# nixie_2020_mainboard_v3_6digit.net
KiCad netlist of a schematic drawn in EAGLE
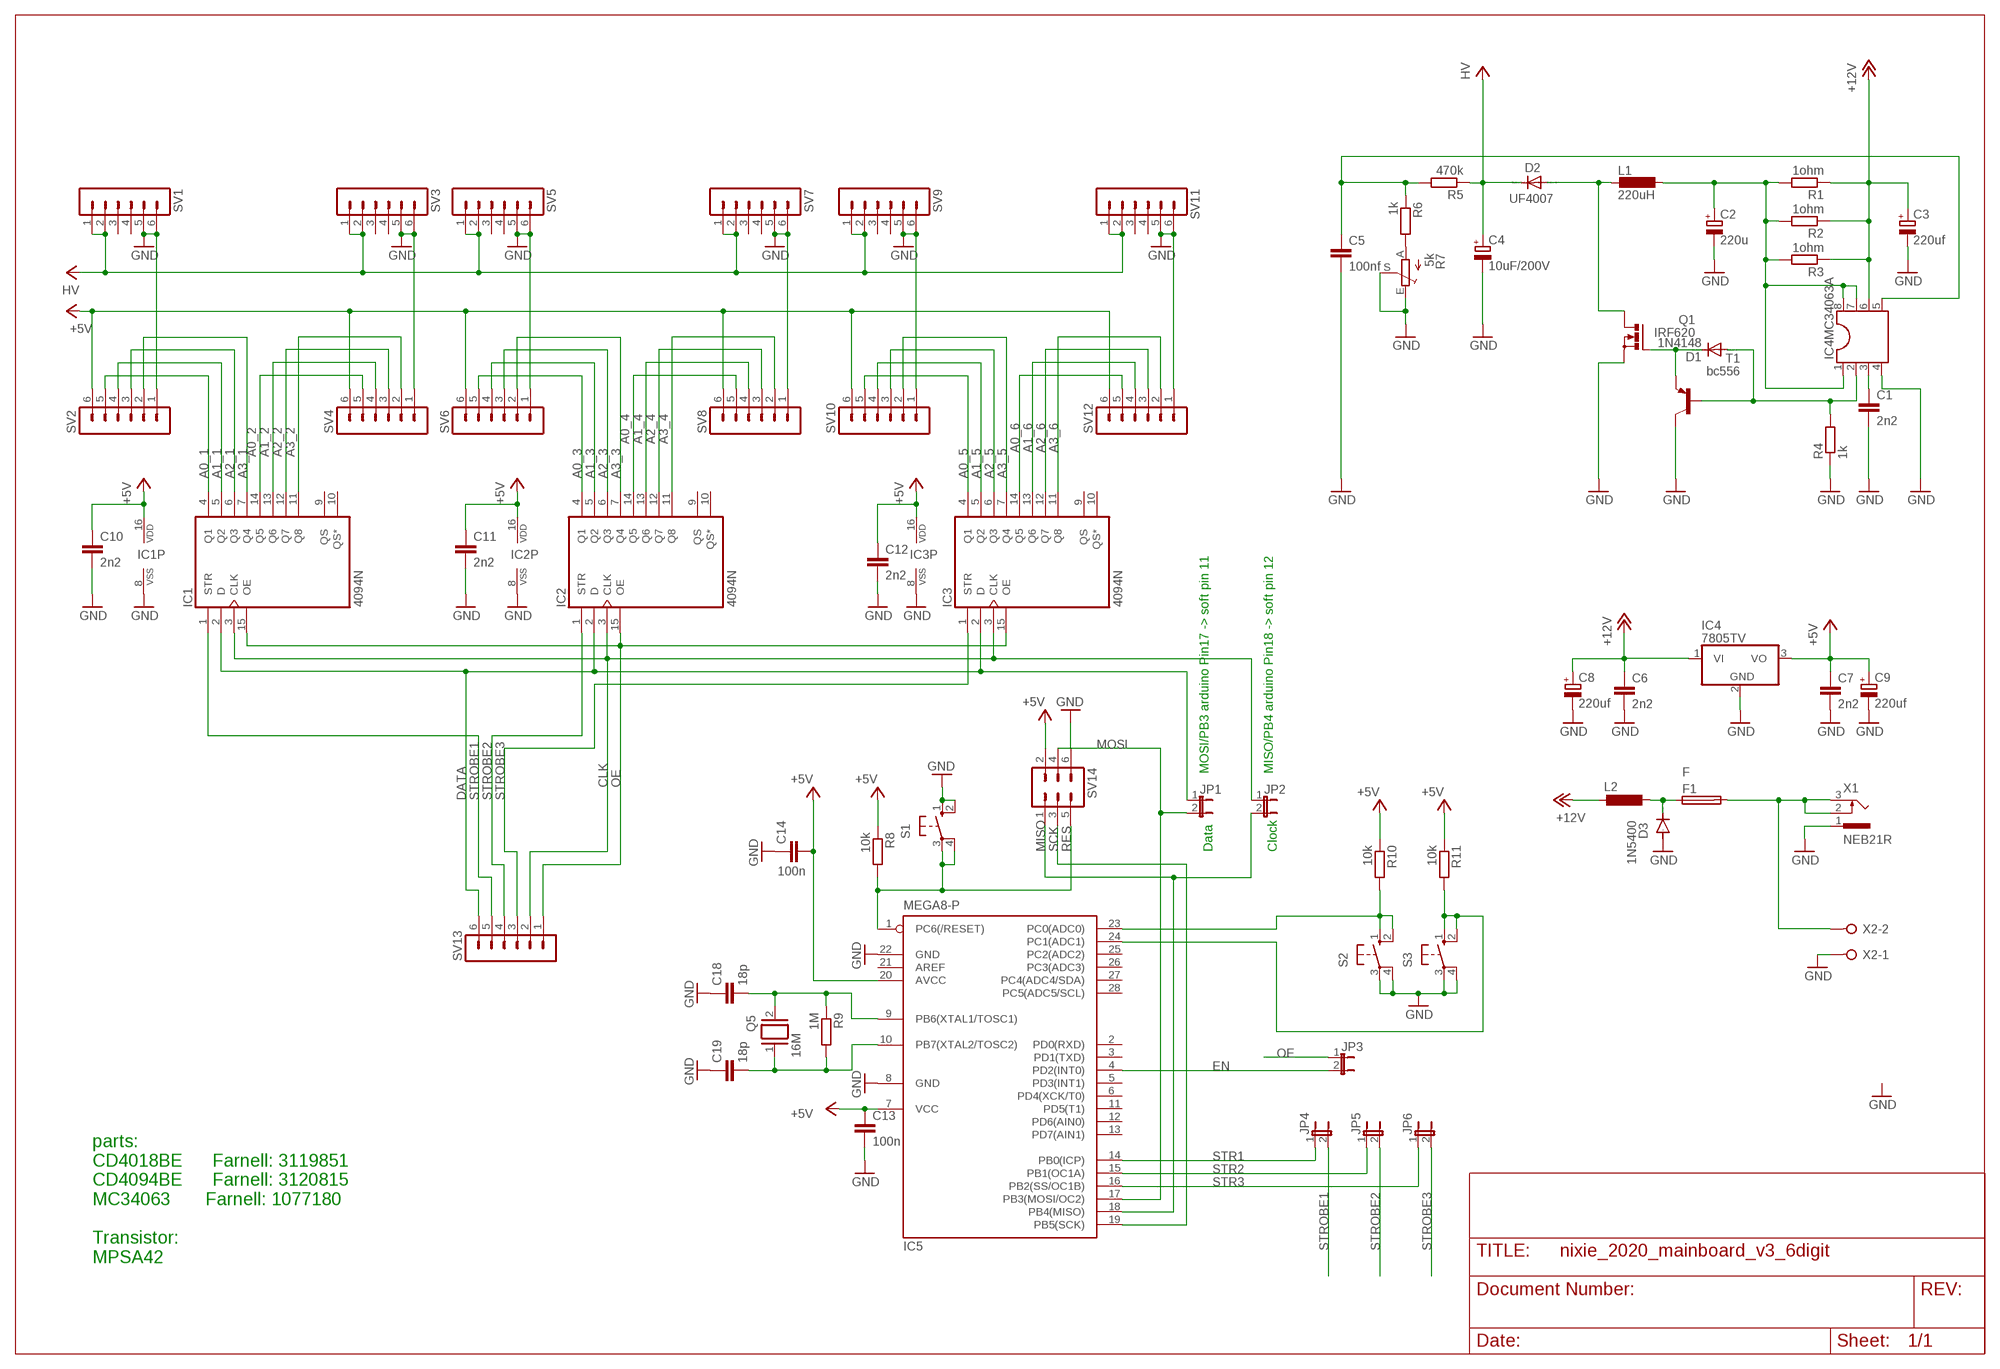
[diagram p0: schematic, sheet 1]

(export (version "E")
  (design (tool "Eeschema 10.0.6"))
  (components
    (comp (ref "C1")
      (value "2n2")
      (footprint "eagle-import:C050-030X075")
      (libsource (lib "eagle-import") (part "C-EU050-030X075"))
    )
    (comp (ref "C2")
      (value "220u")
      (footprint "eagle-import:E5-10,5")
      (libsource (lib "eagle-import") (part "CPOL-EUE5-10.5"))
    )
    (comp (ref "C3")
      (value "220uf")
      (footprint "eagle-import:E5-10,5")
      (libsource (lib "eagle-import") (part "CPOL-EUE5-10.5"))
    )
    (comp (ref "C4")
      (value "10uF/200V")
      (footprint "eagle-import:E5-10,5")
      (libsource (lib "eagle-import") (part "CPOL-EUE5-10.5"))
    )
    (comp (ref "C5")
      (value "100nf")
      (footprint "eagle-import:C075-042X103")
      (libsource (lib "eagle-import") (part "C-EU075-042X103"))
    )
    (comp (ref "C6")
      (value "2n2")
      (footprint "eagle-import:C050-030X075")
      (libsource (lib "eagle-import") (part "C-EU050-030X075"))
    )
    (comp (ref "C7")
      (value "2n2")
      (footprint "eagle-import:C050-030X075")
      (libsource (lib "eagle-import") (part "C-EU050-030X075"))
    )
    (comp (ref "C8")
      (value "220uf")
      (footprint "eagle-import:E5-10,5")
      (libsource (lib "eagle-import") (part "CPOL-EUE5-10.5"))
    )
    (comp (ref "C9")
      (value "220uf")
      (footprint "eagle-import:E5-10,5")
      (libsource (lib "eagle-import") (part "CPOL-EUE5-10.5"))
    )
    (comp (ref "C10")
      (value "2n2")
      (footprint "eagle-import:C050-030X075")
      (libsource (lib "eagle-import") (part "C-EU050-030X075"))
    )
    (comp (ref "C11")
      (value "2n2")
      (footprint "eagle-import:C050-030X075")
      (libsource (lib "eagle-import") (part "C-EU050-030X075"))
    )
    (comp (ref "C12")
      (value "2n2")
      (footprint "eagle-import:C050-030X075")
      (libsource (lib "eagle-import") (part "C-EU050-030X075"))
    )
    (comp (ref "C13")
      (value "100n")
      (footprint "eagle-import:C050-025X075")
      (libsource (lib "eagle-import") (part "resistor_C-EU050-025X075"))
    )
    (comp (ref "C14")
      (value "100n")
      (footprint "eagle-import:C050-025X075")
      (libsource (lib "eagle-import") (part "resistor_C-EU050-025X075"))
    )
    (comp (ref "C18")
      (value "18p")
      (footprint "eagle-import:C050-025X075")
      (libsource (lib "eagle-import") (part "resistor_C-EU050-025X075"))
    )
    (comp (ref "C19")
      (value "18p")
      (footprint "eagle-import:C050-025X075")
      (libsource (lib "eagle-import") (part "resistor_C-EU050-025X075"))
    )
    (comp (ref "D1")
      (value "1N4148")
      (footprint "eagle-import:DO35-10")
      (libsource (lib "eagle-import") (part "1N4148DO35-10"))
    )
    (comp (ref "D2")
      (value "UF4007")
      (footprint "eagle-import:DO35-10")
      (libsource (lib "eagle-import") (part "BAV21"))
    )
    (comp (ref "D3")
      (value "1N5400")
      (footprint "eagle-import:DO201-15")
      (libsource (lib "eagle-import") (part "1N5400"))
    )
    (comp (ref "F1")
      (value "F")
      (footprint "eagle-import:SHK20L")
      (libsource (lib "eagle-import") (part "FUSESHK20L"))
    )
    (comp (ref "IC1")
      (value "4094N")
      (footprint "eagle-import:DIL16")
      (libsource (lib "eagle-import") (part "4094N"))
    )
    (comp (ref "IC2")
      (value "4094N")
      (footprint "eagle-import:DIL16")
      (libsource (lib "eagle-import") (part "4094N"))
    )
    (comp (ref "IC3")
      (value "4094N")
      (footprint "eagle-import:DIL16")
      (libsource (lib "eagle-import") (part "4094N"))
    )
    (comp (ref "IC4")
      (value "7805TV")
      (footprint "eagle-import:TO220V")
      (libsource (lib "eagle-import") (part "78TV05"))
    )
    (comp (ref "IC4MC34063A")
      (value "DIL8S")
      (footprint "eagle-import:SOCKET-08")
      (libsource (lib "eagle-import") (part "DIL8S"))
    )
    (comp (ref "IC5")
      (value "MEGA8-P")
      (footprint "eagle-import:DIL28-3")
      (libsource (lib "eagle-import") (part "MEGA8-P"))
    )
    (comp (ref "JP1")
      (value "JP1E")
      (footprint "eagle-import:JP1")
      (libsource (lib "eagle-import") (part "JP1E"))
    )
    (comp (ref "JP2")
      (value "JP1E")
      (footprint "eagle-import:JP1")
      (libsource (lib "eagle-import") (part "JP1E"))
    )
    (comp (ref "JP3")
      (value "JP1E")
      (footprint "eagle-import:JP1")
      (libsource (lib "eagle-import") (part "JP1E"))
    )
    (comp (ref "JP4")
      (value "JP1E")
      (footprint "eagle-import:JP1")
      (libsource (lib "eagle-import") (part "JP1E"))
    )
    (comp (ref "JP5")
      (value "JP1E")
      (footprint "eagle-import:JP1")
      (libsource (lib "eagle-import") (part "JP1E"))
    )
    (comp (ref "JP6")
      (value "JP1E")
      (footprint "eagle-import:JP1")
      (libsource (lib "eagle-import") (part "JP1E"))
    )
    (comp (ref "L1")
      (value "220uH")
      (footprint "eagle-import:LAN02KR")
      (libsource (lib "eagle-import") (part "L-EULAN02KR"))
    )
    (comp (ref "L2")
      (value "L-EU0207/10")
      (footprint "eagle-import:0207_10")
      (libsource (lib "eagle-import") (part "rcl_334_L-EU0207/10"))
    )
    (comp (ref "Q1")
      (value "IRF620")
      (footprint "eagle-import:TO220BV")
      (libsource (lib "eagle-import") (part "IRF512"))
    )
    (comp (ref "Q5")
      (value "16M")
      (footprint "eagle-import:QS")
      (libsource (lib "eagle-import") (part "XTAL/S"))
    )
    (comp (ref "R1")
      (value "1ohm")
      (footprint "eagle-import:0207_12")
      (libsource (lib "eagle-import") (part "R-EU_0207/12"))
    )
    (comp (ref "R2")
      (value "1ohm")
      (footprint "eagle-import:0207_12")
      (libsource (lib "eagle-import") (part "R-EU_0207/12"))
    )
    (comp (ref "R3")
      (value "1ohm")
      (footprint "eagle-import:0207_12")
      (libsource (lib "eagle-import") (part "R-EU_0207/12"))
    )
    (comp (ref "R4")
      (value "1k")
      (footprint "eagle-import:0207_12")
      (libsource (lib "eagle-import") (part "R-EU_0207/12"))
    )
    (comp (ref "R5")
      (value "470k")
      (footprint "eagle-import:0207_12")
      (libsource (lib "eagle-import") (part "R-EU_0207/12"))
    )
    (comp (ref "R6")
      (value "1k")
      (footprint "eagle-import:0207_12")
      (libsource (lib "eagle-import") (part "R-EU_0207/12"))
    )
    (comp (ref "R7")
      (value "5k")
      (footprint "eagle-import:RJ9W")
      (libsource (lib "eagle-import") (part "TRIM_EU-RJ9W"))
    )
    (comp (ref "R8")
      (value "10k")
      (footprint "eagle-import:0207_12")
      (libsource (lib "eagle-import") (part "R-EU_0207/12"))
    )
    (comp (ref "R9")
      (value "1M")
      (footprint "eagle-import:0207_12")
      (libsource (lib "eagle-import") (part "R-EU_0207/12"))
    )
    (comp (ref "R10")
      (value "10k")
      (footprint "eagle-import:0207_12")
      (libsource (lib "eagle-import") (part "R-EU_0207/12"))
    )
    (comp (ref "R11")
      (value "10k")
      (footprint "eagle-import:0207_12")
      (libsource (lib "eagle-import") (part "R-EU_0207/12"))
    )
    (comp (ref "S1")
      (value "10-XX")
      (footprint "eagle-import:B3F-10XX")
      (fields (field (name "MPN") "B3F-1000"))
      (libsource (lib "eagle-import") (part "10-XX"))
    )
    (comp (ref "S2")
      (value "10-XX")
      (footprint "eagle-import:B3F-10XX")
      (fields (field (name "MPN") "B3F-1000"))
      (libsource (lib "eagle-import") (part "10-XX"))
    )
    (comp (ref "S3")
      (value "10-XX")
      (footprint "eagle-import:B3F-10XX")
      (fields (field (name "MPN") "B3F-1000"))
      (libsource (lib "eagle-import") (part "10-XX"))
    )
    (comp (ref "SV1")
      (value "MA06-1")
      (footprint "eagle-import:MA06-1")
      (libsource (lib "eagle-import") (part "MA06-1"))
    )
    (comp (ref "SV2")
      (value "MA06-1")
      (footprint "eagle-import:MA06-1")
      (libsource (lib "eagle-import") (part "MA06-1"))
    )
    (comp (ref "SV3")
      (value "MA06-1")
      (footprint "eagle-import:MA06-1")
      (libsource (lib "eagle-import") (part "MA06-1"))
    )
    (comp (ref "SV4")
      (value "MA06-1")
      (footprint "eagle-import:MA06-1")
      (libsource (lib "eagle-import") (part "MA06-1"))
    )
    (comp (ref "SV5")
      (value "MA06-1")
      (footprint "eagle-import:MA06-1")
      (libsource (lib "eagle-import") (part "MA06-1"))
    )
    (comp (ref "SV6")
      (value "MA06-1")
      (footprint "eagle-import:MA06-1")
      (libsource (lib "eagle-import") (part "MA06-1"))
    )
    (comp (ref "SV7")
      (value "MA06-1")
      (footprint "eagle-import:MA06-1")
      (libsource (lib "eagle-import") (part "MA06-1"))
    )
    (comp (ref "SV8")
      (value "MA06-1")
      (footprint "eagle-import:MA06-1")
      (libsource (lib "eagle-import") (part "MA06-1"))
    )
    (comp (ref "SV9")
      (value "MA06-1")
      (footprint "eagle-import:MA06-1")
      (libsource (lib "eagle-import") (part "MA06-1"))
    )
    (comp (ref "SV10")
      (value "MA06-1")
      (footprint "eagle-import:MA06-1")
      (libsource (lib "eagle-import") (part "MA06-1"))
    )
    (comp (ref "SV11")
      (value "MA06-1")
      (footprint "eagle-import:MA06-1")
      (libsource (lib "eagle-import") (part "MA06-1"))
    )
    (comp (ref "SV12")
      (value "MA06-1")
      (footprint "eagle-import:MA06-1")
      (libsource (lib "eagle-import") (part "MA06-1"))
    )
    (comp (ref "SV13")
      (value "MA06-1")
      (footprint "eagle-import:MA06-1")
      (libsource (lib "eagle-import") (part "MA06-1"))
    )
    (comp (ref "SV14")
      (value "MA03-2")
      (footprint "eagle-import:MA03-2")
      (libsource (lib "eagle-import") (part "MA03-2"))
    )
    (comp (ref "T1")
      (value "bc556")
      (footprint "eagle-import:TO92-EBC")
      (libsource (lib "eagle-import") (part "-PNP-TO92-EBCBC556A"))
    )
    (comp (ref "X1")
      (value "NEB21R")
      (footprint "eagle-import:NEB21R")
      (fields (field (name "MPN") "NEB 21 R"))
      (libsource (lib "eagle-import") (part "NEB21R"))
    )
    (comp (ref "X2")
      (value "W237-02P")
      (footprint "eagle-import:W237-132")
      (libsource (lib "eagle-import") (part "W237-02P"))
    )
  )
  (nets
    (net (code "1") (name "+5V") (class "Default")
      (node (ref "C10") (pin "1") (pinfunction "1_1") (pintype "passive"))
      (node (ref "C11") (pin "1") (pinfunction "1_1") (pintype "passive"))
      (node (ref "C12") (pin "1") (pinfunction "1_1") (pintype "passive"))
      (node (ref "C13") (pin "1") (pinfunction "1_1") (pintype "passive"))
      (node (ref "C14") (pin "2") (pinfunction "2_2") (pintype "passive"))
      (node (ref "C7") (pin "1") (pinfunction "1_1") (pintype "passive"))
      (node (ref "C9") (pin "+") (pinfunction "+_+") (pintype "passive"))
      (node (ref "IC1") (pin "16") (pinfunction "VDD_16") (pintype "power_in"))
      (node (ref "IC2") (pin "16") (pinfunction "VDD_16") (pintype "power_in"))
      (node (ref "IC3") (pin "16") (pinfunction "VDD_16") (pintype "power_in"))
      (node (ref "IC4") (pin "3") (pinfunction "VO_3") (pintype "passive"))
      (node (ref "IC5") (pin "20") (pinfunction "AVCC_20") (pintype "power_in"))
      (node (ref "IC5") (pin "7") (pinfunction "VCC_7") (pintype "power_in"))
      (node (ref "R10") (pin "1") (pinfunction "1_1") (pintype "passive"))
      (node (ref "R11") (pin "1") (pinfunction "1_1") (pintype "passive"))
      (node (ref "R8") (pin "1") (pinfunction "1_1") (pintype "passive"))
      (node (ref "SV10") (pin "6") (pinfunction "6_6") (pintype "passive"))
      (node (ref "SV12") (pin "6") (pinfunction "6_6") (pintype "passive"))
      (node (ref "SV14") (pin "2") (pinfunction "2_2") (pintype "passive"))
      (node (ref "SV2") (pin "6") (pinfunction "6_6") (pintype "passive"))
      (node (ref "SV4") (pin "6") (pinfunction "6_6") (pintype "passive"))
      (node (ref "SV6") (pin "6") (pinfunction "6_6") (pintype "passive"))
      (node (ref "SV8") (pin "6") (pinfunction "6_6") (pintype "passive"))
    )
    (net (code "2") (name "+12V") (class "Default")
      (node (ref "C3") (pin "+") (pinfunction "+_+") (pintype "passive"))
      (node (ref "C6") (pin "1") (pinfunction "1_1") (pintype "passive"))
      (node (ref "C8") (pin "+") (pinfunction "+_+") (pintype "passive"))
      (node (ref "IC4") (pin "1") (pinfunction "VI_1") (pintype "input"))
      (node (ref "IC4MC34063A") (pin "6") (pinfunction "6_6") (pintype "passive"))
      (node (ref "L2") (pin "1") (pinfunction "1_1") (pintype "passive"))
      (node (ref "R1") (pin "1") (pinfunction "1_1") (pintype "passive"))
      (node (ref "R2") (pin "1") (pinfunction "1_1") (pintype "passive"))
      (node (ref "R3") (pin "1") (pinfunction "1_1") (pintype "passive"))
    )
    (net (code "3") (name "/A0_1") (class "Default")
      (node (ref "IC1") (pin "4") (pinfunction "Q1_4") (pintype "output"))
      (node (ref "SV2") (pin "5") (pinfunction "5_5") (pintype "passive"))
    )
    (net (code "4") (name "/A0_2") (class "Default")
      (node (ref "IC1") (pin "14") (pinfunction "Q5_14") (pintype "output"))
      (node (ref "SV4") (pin "5") (pinfunction "5_5") (pintype "passive"))
    )
    (net (code "5") (name "/A0_3") (class "Default")
      (node (ref "IC2") (pin "4") (pinfunction "Q1_4") (pintype "output"))
      (node (ref "SV6") (pin "5") (pinfunction "5_5") (pintype "passive"))
    )
    (net (code "6") (name "/A0_4") (class "Default")
      (node (ref "IC2") (pin "14") (pinfunction "Q5_14") (pintype "output"))
      (node (ref "SV8") (pin "5") (pinfunction "5_5") (pintype "passive"))
    )
    (net (code "7") (name "/A0_5") (class "Default")
      (node (ref "IC3") (pin "4") (pinfunction "Q1_4") (pintype "output"))
      (node (ref "SV10") (pin "5") (pinfunction "5_5") (pintype "passive"))
    )
    (net (code "8") (name "/A0_6") (class "Default")
      (node (ref "IC3") (pin "14") (pinfunction "Q5_14") (pintype "output"))
      (node (ref "SV12") (pin "5") (pinfunction "5_5") (pintype "passive"))
    )
    (net (code "9") (name "/A1_1") (class "Default")
      (node (ref "IC1") (pin "5") (pinfunction "Q2_5") (pintype "output"))
      (node (ref "SV2") (pin "4") (pinfunction "4_4") (pintype "passive"))
    )
    (net (code "10") (name "/A1_2") (class "Default")
      (node (ref "IC1") (pin "13") (pinfunction "Q6_13") (pintype "output"))
      (node (ref "SV4") (pin "4") (pinfunction "4_4") (pintype "passive"))
    )
    (net (code "11") (name "/A1_3") (class "Default")
      (node (ref "IC2") (pin "5") (pinfunction "Q2_5") (pintype "output"))
      (node (ref "SV6") (pin "4") (pinfunction "4_4") (pintype "passive"))
    )
    (net (code "12") (name "/A1_4") (class "Default")
      (node (ref "IC2") (pin "13") (pinfunction "Q6_13") (pintype "output"))
      (node (ref "SV8") (pin "4") (pinfunction "4_4") (pintype "passive"))
    )
    (net (code "13") (name "/A1_5") (class "Default")
      (node (ref "IC3") (pin "5") (pinfunction "Q2_5") (pintype "output"))
      (node (ref "SV10") (pin "4") (pinfunction "4_4") (pintype "passive"))
    )
    (net (code "14") (name "/A1_6") (class "Default")
      (node (ref "IC3") (pin "13") (pinfunction "Q6_13") (pintype "output"))
      (node (ref "SV12") (pin "4") (pinfunction "4_4") (pintype "passive"))
    )
    (net (code "15") (name "/A2_1") (class "Default")
      (node (ref "IC1") (pin "6") (pinfunction "Q3_6") (pintype "output"))
      (node (ref "SV2") (pin "3") (pinfunction "3_3") (pintype "passive"))
    )
    (net (code "16") (name "/A2_2") (class "Default")
      (node (ref "IC1") (pin "12") (pinfunction "Q7_12") (pintype "output"))
      (node (ref "SV4") (pin "3") (pinfunction "3_3") (pintype "passive"))
    )
    (net (code "17") (name "/A2_3") (class "Default")
      (node (ref "IC2") (pin "6") (pinfunction "Q3_6") (pintype "output"))
      (node (ref "SV6") (pin "3") (pinfunction "3_3") (pintype "passive"))
    )
    (net (code "18") (name "/A2_4") (class "Default")
      (node (ref "IC2") (pin "12") (pinfunction "Q7_12") (pintype "output"))
      (node (ref "SV8") (pin "3") (pinfunction "3_3") (pintype "passive"))
    )
    (net (code "19") (name "/A2_5") (class "Default")
      (node (ref "IC3") (pin "6") (pinfunction "Q3_6") (pintype "output"))
      (node (ref "SV10") (pin "3") (pinfunction "3_3") (pintype "passive"))
    )
    (net (code "20") (name "/A2_6") (class "Default")
      (node (ref "IC3") (pin "12") (pinfunction "Q7_12") (pintype "output"))
      (node (ref "SV12") (pin "3") (pinfunction "3_3") (pintype "passive"))
    )
    (net (code "21") (name "/A3_1") (class "Default")
      (node (ref "IC1") (pin "7") (pinfunction "Q4_7") (pintype "output"))
      (node (ref "SV2") (pin "2") (pinfunction "2_2") (pintype "passive"))
    )
    (net (code "22") (name "/A3_2") (class "Default")
      (node (ref "IC1") (pin "11") (pinfunction "Q8_11") (pintype "output"))
      (node (ref "SV4") (pin "2") (pinfunction "2_2") (pintype "passive"))
    )
    (net (code "23") (name "/A3_3") (class "Default")
      (node (ref "IC2") (pin "7") (pinfunction "Q4_7") (pintype "output"))
      (node (ref "SV6") (pin "2") (pinfunction "2_2") (pintype "passive"))
    )
    (net (code "24") (name "/A3_4") (class "Default")
      (node (ref "IC2") (pin "11") (pinfunction "Q8_11") (pintype "output"))
      (node (ref "SV8") (pin "2") (pinfunction "2_2") (pintype "passive"))
    )
    (net (code "25") (name "/A3_5") (class "Default")
      (node (ref "IC3") (pin "7") (pinfunction "Q4_7") (pintype "output"))
      (node (ref "SV10") (pin "2") (pinfunction "2_2") (pintype "passive"))
    )
    (net (code "26") (name "/A3_6") (class "Default")
      (node (ref "IC3") (pin "11") (pinfunction "Q8_11") (pintype "output"))
      (node (ref "SV12") (pin "2") (pinfunction "2_2") (pintype "passive"))
    )
    (net (code "27") (name "/CLK") (class "Default")
      (node (ref "IC1") (pin "3") (pinfunction "CLK_3") (pintype "input"))
      (node (ref "IC2") (pin "3") (pinfunction "CLK_3") (pintype "input"))
      (node (ref "IC3") (pin "3") (pinfunction "CLK_3") (pintype "input"))
      (node (ref "JP2") (pin "1") (pinfunction "1_1") (pintype "passive"))
      (node (ref "SV13") (pin "2") (pinfunction "2_2") (pintype "passive"))
    )
    (net (code "28") (name "/DATA") (class "Default")
      (node (ref "IC1") (pin "2") (pinfunction "D_2") (pintype "input"))
      (node (ref "IC2") (pin "2") (pinfunction "D_2") (pintype "input"))
      (node (ref "IC3") (pin "2") (pinfunction "D_2") (pintype "input"))
      (node (ref "JP1") (pin "1") (pinfunction "1_1") (pintype "passive"))
      (node (ref "SV13") (pin "6") (pinfunction "6_6") (pintype "passive"))
    )
    (net (code "29") (name "/EN") (class "Default")
      (node (ref "IC5") (pin "4") (pinfunction "PD2(INT0)_4") (pintype "bidirectional"))
      (node (ref "JP3") (pin "2") (pinfunction "2_2") (pintype "passive"))
    )
    (net (code "30") (name "/MISO") (class "Default")
      (node (ref "IC5") (pin "18") (pinfunction "PB4(MISO)_18") (pintype "bidirectional"))
      (node (ref "JP2") (pin "2") (pinfunction "2_2") (pintype "passive"))
      (node (ref "SV14") (pin "1") (pinfunction "1_1") (pintype "passive"))
    )
    (net (code "31") (name "/MOSI") (class "Default")
      (node (ref "IC5") (pin "17") (pinfunction "PB3(MOSI/OC2)_17") (pintype "bidirectional"))
      (node (ref "JP1") (pin "2") (pinfunction "2_2") (pintype "passive"))
      (node (ref "SV14") (pin "4") (pinfunction "4_4") (pintype "passive"))
    )
    (net (code "32") (name "/OE") (class "Default")
      (node (ref "IC1") (pin "15") (pinfunction "OE_15") (pintype "input"))
      (node (ref "IC2") (pin "15") (pinfunction "OE_15") (pintype "input"))
      (node (ref "IC3") (pin "15") (pinfunction "OE_15") (pintype "input"))
      (node (ref "JP3") (pin "1") (pinfunction "1_1") (pintype "passive"))
      (node (ref "SV13") (pin "1") (pinfunction "1_1") (pintype "passive"))
    )
    (net (code "33") (name "/RES") (class "Default")
      (node (ref "IC5") (pin "1") (pinfunction "PC6(/RESET)_1") (pintype "bidirectional"))
      (node (ref "R8") (pin "2") (pinfunction "2_2") (pintype "passive"))
      (node (ref "S1") (pin "3") (pinfunction "P_3") (pintype "passive"))
      (node (ref "S1") (pin "4") (pinfunction "P1_4") (pintype "passive"))
      (node (ref "SV14") (pin "5") (pinfunction "5_5") (pintype "passive"))
    )
    (net (code "34") (name "/SCK") (class "Default")
      (node (ref "IC5") (pin "19") (pinfunction "PB5(SCK)_19") (pintype "bidirectional"))
      (node (ref "SV14") (pin "3") (pinfunction "3_3") (pintype "passive"))
    )
    (net (code "35") (name "/STR1") (class "Default")
      (node (ref "IC5") (pin "14") (pinfunction "PB0(ICP)_14") (pintype "bidirectional"))
      (node (ref "JP4") (pin "1") (pinfunction "1_1") (pintype "passive"))
    )
    (net (code "36") (name "/STR2") (class "Default")
      (node (ref "IC5") (pin "15") (pinfunction "PB1(OC1A)_15") (pintype "bidirectional"))
      (node (ref "JP5") (pin "1") (pinfunction "1_1") (pintype "passive"))
    )
    (net (code "37") (name "/STR3") (class "Default")
      (node (ref "IC5") (pin "16") (pinfunction "PB2(SS/OC1B)_16") (pintype "bidirectional"))
      (node (ref "JP6") (pin "1") (pinfunction "1_1") (pintype "passive"))
    )
    (net (code "38") (name "/STROBE1") (class "Default")
      (node (ref "IC1") (pin "1") (pinfunction "STR_1") (pintype "input"))
      (node (ref "JP4") (pin "2") (pinfunction "2_2") (pintype "passive"))
      (node (ref "SV13") (pin "5") (pinfunction "5_5") (pintype "passive"))
    )
    (net (code "39") (name "/STROBE2") (class "Default")
      (node (ref "IC2") (pin "1") (pinfunction "STR_1") (pintype "input"))
      (node (ref "JP5") (pin "2") (pinfunction "2_2") (pintype "passive"))
      (node (ref "SV13") (pin "4") (pinfunction "4_4") (pintype "passive"))
    )
    (net (code "40") (name "/STROBE3") (class "Default")
      (node (ref "IC3") (pin "1") (pinfunction "STR_1") (pintype "input"))
      (node (ref "JP6") (pin "2") (pinfunction "2_2") (pintype "passive"))
      (node (ref "SV13") (pin "3") (pinfunction "3_3") (pintype "passive"))
    )
    (net (code "41") (name "GND") (class "Default")
      (node (ref "C1") (pin "2") (pinfunction "2_2") (pintype "passive"))
      (node (ref "C10") (pin "2") (pinfunction "2_2") (pintype "passive"))
      (node (ref "C11") (pin "2") (pinfunction "2_2") (pintype "passive"))
      (node (ref "C12") (pin "2") (pinfunction "2_2") (pintype "passive"))
      (node (ref "C13") (pin "2") (pinfunction "2_2") (pintype "passive"))
      (node (ref "C14") (pin "1") (pinfunction "1_1") (pintype "passive"))
      (node (ref "C18") (pin "1") (pinfunction "1_1") (pintype "passive"))
      (node (ref "C19") (pin "1") (pinfunction "1_1") (pintype "passive"))
      (node (ref "C2") (pin "-") (pinfunction "-_-") (pintype "passive"))
      (node (ref "C3") (pin "-") (pinfunction "-_-") (pintype "passive"))
      (node (ref "C4") (pin "-") (pinfunction "-_-") (pintype "passive"))
      (node (ref "C5") (pin "2") (pinfunction "2_2") (pintype "passive"))
      (node (ref "C6") (pin "2") (pinfunction "2_2") (pintype "passive"))
      (node (ref "C7") (pin "2") (pinfunction "2_2") (pintype "passive"))
      (node (ref "C8") (pin "-") (pinfunction "-_-") (pintype "passive"))
      (node (ref "C9") (pin "-") (pinfunction "-_-") (pintype "passive"))
      (node (ref "D3") (pin "A") (pinfunction "A_A") (pintype "passive"))
      (node (ref "IC1") (pin "8") (pinfunction "VSS_8") (pintype "power_in"))
      (node (ref "IC2") (pin "8") (pinfunction "VSS_8") (pintype "power_in"))
      (node (ref "IC3") (pin "8") (pinfunction "VSS_8") (pintype "power_in"))
      (node (ref "IC4") (pin "2") (pinfunction "GND_2") (pintype "passive"))
      (node (ref "IC4MC34063A") (pin "4") (pinfunction "4_4") (pintype "passive"))
      (node (ref "IC5") (pin "22") (pinfunction "GND_22") (pintype "power_in"))
      (node (ref "IC5") (pin "8") (pinfunction "GND_8") (pintype "power_in"))
      (node (ref "Q1") (pin "S") (pinfunction "S_S") (pintype "passive"))
      (node (ref "R4") (pin "1") (pinfunction "1_1") (pintype "passive"))
      (node (ref "R7") (pin "E") (pinfunction "E_E") (pintype "passive"))
      (node (ref "R7") (pin "S") (pinfunction "S_S") (pintype "passive"))
      (node (ref "S1") (pin "1") (pinfunction "S_1") (pintype "passive"))
      (node (ref "S1") (pin "2") (pinfunction "S1_2") (pintype "passive"))
      (node (ref "S2") (pin "3") (pinfunction "P_3") (pintype "passive"))
      (node (ref "S2") (pin "4") (pinfunction "P1_4") (pintype "passive"))
      (node (ref "S3") (pin "3") (pinfunction "P_3") (pintype "passive"))
      (node (ref "S3") (pin "4") (pinfunction "P1_4") (pintype "passive"))
      (node (ref "SV1") (pin "5") (pinfunction "5_5") (pintype "passive"))
      (node (ref "SV1") (pin "6") (pinfunction "6_6") (pintype "passive"))
      (node (ref "SV10") (pin "1") (pinfunction "1_1") (pintype "passive"))
      (node (ref "SV11") (pin "5") (pinfunction "5_5") (pintype "passive"))
      (node (ref "SV11") (pin "6") (pinfunction "6_6") (pintype "passive"))
      (node (ref "SV12") (pin "1") (pinfunction "1_1") (pintype "passive"))
      (node (ref "SV14") (pin "6") (pinfunction "6_6") (pintype "passive"))
      (node (ref "SV2") (pin "1") (pinfunction "1_1") (pintype "passive"))
      (node (ref "SV3") (pin "5") (pinfunction "5_5") (pintype "passive"))
      (node (ref "SV3") (pin "6") (pinfunction "6_6") (pintype "passive"))
      (node (ref "SV4") (pin "1") (pinfunction "1_1") (pintype "passive"))
      (node (ref "SV5") (pin "5") (pinfunction "5_5") (pintype "passive"))
      (node (ref "SV5") (pin "6") (pinfunction "6_6") (pintype "passive"))
      (node (ref "SV6") (pin "1") (pinfunction "1_1") (pintype "passive"))
      (node (ref "SV7") (pin "5") (pinfunction "5_5") (pintype "passive"))
      (node (ref "SV7") (pin "6") (pinfunction "6_6") (pintype "passive"))
      (node (ref "SV8") (pin "1") (pinfunction "1_1") (pintype "passive"))
      (node (ref "SV9") (pin "5") (pinfunction "5_5") (pintype "passive"))
      (node (ref "SV9") (pin "6") (pinfunction "6_6") (pintype "passive"))
      (node (ref "T1") (pin "C") (pinfunction "C_C") (pintype "passive"))
      (node (ref "X1") (pin "1") (pinfunction "1_1") (pintype "passive"))
      (node (ref "X2") (pin "1") (pinfunction "KL_1") (pintype "passive"))
    )
    (net (code "42") (name "HV") (class "Default")
      (node (ref "C4") (pin "+") (pinfunction "+_+") (pintype "passive"))
      (node (ref "D2") (pin "C") (pinfunction "C_C") (pintype "passive"))
      (node (ref "R5") (pin "1") (pinfunction "1_1") (pintype "passive"))
      (node (ref "SV1") (pin "1") (pinfunction "1_1") (pintype "passive"))
      (node (ref "SV1") (pin "2") (pinfunction "2_2") (pintype "passive"))
      (node (ref "SV11") (pin "1") (pinfunction "1_1") (pintype "passive"))
      (node (ref "SV11") (pin "2") (pinfunction "2_2") (pintype "passive"))
      (node (ref "SV3") (pin "1") (pinfunction "1_1") (pintype "passive"))
      (node (ref "SV3") (pin "2") (pinfunction "2_2") (pintype "passive"))
      (node (ref "SV5") (pin "1") (pinfunction "1_1") (pintype "passive"))
      (node (ref "SV5") (pin "2") (pinfunction "2_2") (pintype "passive"))
      (node (ref "SV7") (pin "1") (pinfunction "1_1") (pintype "passive"))
      (node (ref "SV7") (pin "2") (pinfunction "2_2") (pintype "passive"))
      (node (ref "SV9") (pin "1") (pinfunction "1_1") (pintype "passive"))
      (node (ref "SV9") (pin "2") (pinfunction "2_2") (pintype "passive"))
    )
    (net (code "43") (name "Net-(C1-Pad1)") (class "Default")
      (node (ref "C1") (pin "1") (pinfunction "1_1") (pintype "passive"))
      (node (ref "IC4MC34063A") (pin "3") (pinfunction "3_3") (pintype "passive"))
    )
    (net (code "44") (name "Net-(C2-Pad+)") (class "Default")
      (node (ref "C2") (pin "+") (pinfunction "+_+") (pintype "passive"))
      (node (ref "IC4MC34063A") (pin "1") (pinfunction "1_1") (pintype "passive"))
      (node (ref "IC4MC34063A") (pin "7") (pinfunction "7_7") (pintype "passive"))
      (node (ref "IC4MC34063A") (pin "8") (pinfunction "8_8") (pintype "passive"))
      (node (ref "L1") (pin "1") (pinfunction "1_1") (pintype "passive"))
      (node (ref "R1") (pin "2") (pinfunction "2_2") (pintype "passive"))
      (node (ref "R2") (pin "2") (pinfunction "2_2") (pintype "passive"))
      (node (ref "R3") (pin "2") (pinfunction "2_2") (pintype "passive"))
    )
    (net (code "45") (name "Net-(C5-Pad1)") (class "Default")
      (node (ref "C5") (pin "1") (pinfunction "1_1") (pintype "passive"))
      (node (ref "IC4MC34063A") (pin "5") (pinfunction "5_5") (pintype "passive"))
      (node (ref "R5") (pin "2") (pinfunction "2_2") (pintype "passive"))
      (node (ref "R6") (pin "1") (pinfunction "1_1") (pintype "passive"))
    )
    (net (code "46") (name "Net-(D1-PadA)") (class "Default")
      (node (ref "D1") (pin "A") (pinfunction "A_A") (pintype "passive"))
      (node (ref "IC4MC34063A") (pin "2") (pinfunction "2_2") (pintype "passive"))
      (node (ref "R4") (pin "2") (pinfunction "2_2") (pintype "passive"))
      (node (ref "T1") (pin "B") (pinfunction "B_B") (pintype "passive"))
    )
    (net (code "47") (name "Net-(D1-PadC)") (class "Default")
      (node (ref "D1") (pin "C") (pinfunction "C_C") (pintype "passive"))
      (node (ref "Q1") (pin "G") (pinfunction "G_G") (pintype "passive"))
      (node (ref "T1") (pin "E") (pinfunction "E_E") (pintype "passive"))
    )
    (net (code "48") (name "Net-(D2-PadA)") (class "Default")
      (node (ref "D2") (pin "A") (pinfunction "A_A") (pintype "passive"))
      (node (ref "L1") (pin "2") (pinfunction "2_2") (pintype "passive"))
      (node (ref "Q1") (pin "D") (pinfunction "D_D") (pintype "passive"))
    )
    (net (code "49") (name "Net-(F1-1)") (class "Default")
      (node (ref "D3") (pin "C") (pinfunction "C_C") (pintype "passive"))
      (node (ref "F1") (pin "1A") (pinfunction "1_1A") (pintype "passive"))
      (node (ref "L2") (pin "2") (pinfunction "2_2") (pintype "passive"))
    )
    (net (code "50") (name "Net-(F1-2)") (class "Default")
      (node (ref "F1") (pin "2A") (pinfunction "2_2A") (pintype "passive"))
      (node (ref "X1") (pin "2") (pinfunction "2_2") (pintype "passive"))
      (node (ref "X1") (pin "3") (pinfunction "3_3") (pintype "passive"))
      (node (ref "X2") (pin "2") (pinfunction "KL_2") (pintype "passive"))
    )
    (net (code "51") (name "Net-(IC5-PB6(XTAL1{slash}TOSC1))") (class "Default")
      (node (ref "C18") (pin "2") (pinfunction "2_2") (pintype "passive"))
      (node (ref "IC5") (pin "9") (pinfunction "PB6(XTAL1/TOSC1)_9") (pintype "bidirectional"))
      (node (ref "Q5") (pin "2") (pinfunction "2_2") (pintype "passive"))
      (node (ref "R9") (pin "1") (pinfunction "1_1") (pintype "passive"))
    )
    (net (code "52") (name "Net-(IC5-PB7(XTAL2{slash}TOSC2))") (class "Default")
      (node (ref "C19") (pin "2") (pinfunction "2_2") (pintype "passive"))
      (node (ref "IC5") (pin "10") (pinfunction "PB7(XTAL2/TOSC2)_10") (pintype "bidirectional"))
      (node (ref "Q5") (pin "1") (pinfunction "1_1") (pintype "passive"))
      (node (ref "R9") (pin "2") (pinfunction "2_2") (pintype "passive"))
    )
    (net (code "53") (name "Net-(IC5-PC0(ADC0))") (class "Default")
      (node (ref "IC5") (pin "23") (pinfunction "PC0(ADC0)_23") (pintype "bidirectional"))
      (node (ref "R10") (pin "2") (pinfunction "2_2") (pintype "passive"))
      (node (ref "S2") (pin "1") (pinfunction "S_1") (pintype "passive"))
      (node (ref "S2") (pin "2") (pinfunction "S1_2") (pintype "passive"))
    )
    (net (code "54") (name "Net-(IC5-PC1(ADC1))") (class "Default")
      (node (ref "IC5") (pin "24") (pinfunction "PC1(ADC1)_24") (pintype "bidirectional"))
      (node (ref "R11") (pin "2") (pinfunction "2_2") (pintype "passive"))
      (node (ref "S3") (pin "1") (pinfunction "S_1") (pintype "passive"))
      (node (ref "S3") (pin "2") (pinfunction "S1_2") (pintype "passive"))
    )
    (net (code "55") (name "Net-(R6-Pad2)") (class "Default")
      (node (ref "R6") (pin "2") (pinfunction "2_2") (pintype "passive"))
      (node (ref "R7") (pin "A") (pinfunction "A_A") (pintype "passive"))
    )
    (net (code "56") (name "unconnected-(IC1A-QS*-Pad10)") (class "Default")
      (node (ref "IC1") (pin "10") (pinfunction "QS*_10") (pintype "output"))
    )
    (net (code "57") (name "unconnected-(IC1A-QS-Pad9)") (class "Default")
      (node (ref "IC1") (pin "9") (pinfunction "QS_9") (pintype "output"))
    )
    (net (code "58") (name "unconnected-(IC2A-QS*-Pad10)") (class "Default")
      (node (ref "IC2") (pin "10") (pinfunction "QS*_10") (pintype "output"))
    )
    (net (code "59") (name "unconnected-(IC2A-QS-Pad9)") (class "Default")
      (node (ref "IC2") (pin "9") (pinfunction "QS_9") (pintype "output"))
    )
    (net (code "60") (name "unconnected-(IC3A-QS*-Pad10)") (class "Default")
      (node (ref "IC3") (pin "10") (pinfunction "QS*_10") (pintype "output"))
    )
    (net (code "61") (name "unconnected-(IC3A-QS-Pad9)") (class "Default")
      (node (ref "IC3") (pin "9") (pinfunction "QS_9") (pintype "output"))
    )
    (net (code "62") (name "unconnected-(IC5-AREF-Pad21)") (class "Default")
      (node (ref "IC5") (pin "21") (pinfunction "AREF_21") (pintype "passive"))
    )
    (net (code "63") (name "unconnected-(IC5-PC2(ADC2)-Pad25)") (class "Default")
      (node (ref "IC5") (pin "25") (pinfunction "PC2(ADC2)_25") (pintype "bidirectional"))
    )
    (net (code "64") (name "unconnected-(IC5-PC3(ADC3)-Pad26)") (class "Default")
      (node (ref "IC5") (pin "26") (pinfunction "PC3(ADC3)_26") (pintype "bidirectional"))
    )
    (net (code "65") (name "unconnected-(IC5-PC4(ADC4{slash}SDA)-Pad27)") (class "Default")
      (node (ref "IC5") (pin "27") (pinfunction "PC4(ADC4/SDA)_27") (pintype "bidirectional"))
    )
    (net (code "66") (name "unconnected-(IC5-PC5(ADC5{slash}SCL)-Pad28)") (class "Default")
      (node (ref "IC5") (pin "28") (pinfunction "PC5(ADC5/SCL)_28") (pintype "bidirectional"))
    )
    (net (code "67") (name "unconnected-(IC5-PD0(RXD)-Pad2)") (class "Default")
      (node (ref "IC5") (pin "2") (pinfunction "PD0(RXD)_2") (pintype "bidirectional"))
    )
    (net (code "68") (name "unconnected-(IC5-PD1(TXD)-Pad3)") (class "Default")
      (node (ref "IC5") (pin "3") (pinfunction "PD1(TXD)_3") (pintype "bidirectional"))
    )
    (net (code "69") (name "unconnected-(IC5-PD3(INT1)-Pad5)") (class "Default")
      (node (ref "IC5") (pin "5") (pinfunction "PD3(INT1)_5") (pintype "bidirectional"))
    )
    (net (code "70") (name "unconnected-(IC5-PD4(XCK{slash}T0)-Pad6)") (class "Default")
      (node (ref "IC5") (pin "6") (pinfunction "PD4(XCK/T0)_6") (pintype "bidirectional"))
    )
    (net (code "71") (name "unconnected-(IC5-PD5(T1)-Pad11)") (class "Default")
      (node (ref "IC5") (pin "11") (pinfunction "PD5(T1)_11") (pintype "bidirectional"))
    )
    (net (code "72") (name "unconnected-(IC5-PD6(AIN0)-Pad12)") (class "Default")
      (node (ref "IC5") (pin "12") (pinfunction "PD6(AIN0)_12") (pintype "bidirectional"))
    )
    (net (code "73") (name "unconnected-(IC5-PD7(AIN1)-Pad13)") (class "Default")
      (node (ref "IC5") (pin "13") (pinfunction "PD7(AIN1)_13") (pintype "bidirectional"))
    )
    (net (code "74") (name "unconnected-(SV1-Pad3)") (class "Default")
      (node (ref "SV1") (pin "3") (pinfunction "3_3") (pintype "passive"))
    )
    (net (code "75") (name "unconnected-(SV1-Pad4)") (class "Default")
      (node (ref "SV1") (pin "4") (pinfunction "4_4") (pintype "passive"))
    )
    (net (code "76") (name "unconnected-(SV3-Pad3)") (class "Default")
      (node (ref "SV3") (pin "3") (pinfunction "3_3") (pintype "passive"))
    )
    (net (code "77") (name "unconnected-(SV3-Pad4)") (class "Default")
      (node (ref "SV3") (pin "4") (pinfunction "4_4") (pintype "passive"))
    )
    (net (code "78") (name "unconnected-(SV5-Pad3)") (class "Default")
      (node (ref "SV5") (pin "3") (pinfunction "3_3") (pintype "passive"))
    )
    (net (code "79") (name "unconnected-(SV5-Pad4)") (class "Default")
      (node (ref "SV5") (pin "4") (pinfunction "4_4") (pintype "passive"))
    )
    (net (code "80") (name "unconnected-(SV7-Pad3)") (class "Default")
      (node (ref "SV7") (pin "3") (pinfunction "3_3") (pintype "passive"))
    )
    (net (code "81") (name "unconnected-(SV7-Pad4)") (class "Default")
      (node (ref "SV7") (pin "4") (pinfunction "4_4") (pintype "passive"))
    )
    (net (code "82") (name "unconnected-(SV9-Pad3)") (class "Default")
      (node (ref "SV9") (pin "3") (pinfunction "3_3") (pintype "passive"))
    )
    (net (code "83") (name "unconnected-(SV9-Pad4)") (class "Default")
      (node (ref "SV9") (pin "4") (pinfunction "4_4") (pintype "passive"))
    )
    (net (code "84") (name "unconnected-(SV11-Pad3)") (class "Default")
      (node (ref "SV11") (pin "3") (pinfunction "3_3") (pintype "passive"))
    )
    (net (code "85") (name "unconnected-(SV11-Pad4)") (class "Default")
      (node (ref "SV11") (pin "4") (pinfunction "4_4") (pintype "passive"))
    )
  )
)
